# USBC.net
KiCad netlist of a schematic drawn in Altium Designer
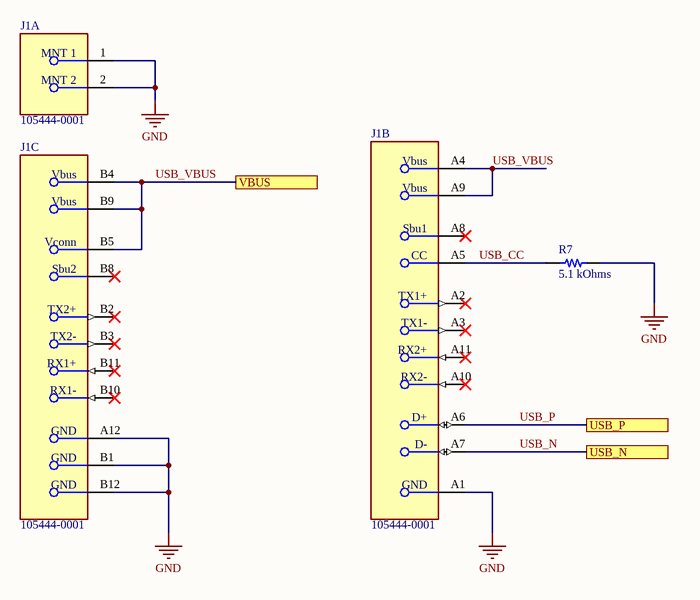
[diagram p0: USBC.SchDoc]

(export (version "E")
  (design (tool "Eeschema 10.0.6"))
  (components
    (comp (ref "J1")
      (value "105444-0001")
      (footprint "FP-105444-0001-MFG")
      (description "CONN PLUG USB3.1 TYPEC BRD EDGE")
      (libsource (lib "Altium Content Vault") (part "182575ff53d3110fee9f5872a599f53"))
    )
    (comp (ref "R7")
      (value "5.1 kOhms")
      (footprint "RES 0603_1608")
      (description "RES 5.1K OHM 0.1% 1/10W 0603")
      (fields (field (name "PART NUMBER") "TNPW06035K10BYEN") (field (name "MANUFACTURER") "Vishay Dale"))
      (libsource (lib "Celestial Altium Library - altium_library") (part "Resistor"))
    )
  )
  (nets
    (net (code "1") (name "/USB_CC") (class "Default")
      (node (ref "J1") (pin "A5") (pinfunction "CC_A5") (pintype "passive"))
      (node (ref "R7") (pin "1") (pinfunction "1_1") (pintype "passive"))
    )
    (net (code "2") (name "/USB_N") (class "Default")
      (node (ref "J1") (pin "A7") (pinfunction "D-_A7") (pintype "bidirectional"))
    )
    (net (code "3") (name "/USB_P") (class "Default")
      (node (ref "J1") (pin "A6") (pinfunction "D+_A6") (pintype "bidirectional"))
    )
    (net (code "4") (name "/USB_VBUS") (class "Default")
      (node (ref "J1") (pin "A4") (pinfunction "Vbus_A4") (pintype "power_in"))
      (node (ref "J1") (pin "A9") (pinfunction "Vbus_A9") (pintype "power_in"))
      (node (ref "J1") (pin "B4") (pinfunction "Vbus_B4") (pintype "power_in"))
      (node (ref "J1") (pin "B5") (pinfunction "Vconn_B5") (pintype "power_in"))
      (node (ref "J1") (pin "B9") (pinfunction "Vbus_B9") (pintype "power_in"))
    )
    (net (code "5") (name "GND") (class "Default")
      (node (ref "J1") (pin "1") (pinfunction "MNT_1_1") (pintype "passive"))
      (node (ref "J1") (pin "2") (pinfunction "MNT_2_2") (pintype "passive"))
      (node (ref "J1") (pin "A1") (pinfunction "GND_A1") (pintype "power_in"))
      (node (ref "J1") (pin "A12") (pinfunction "GND_A12") (pintype "power_in"))
      (node (ref "J1") (pin "B1") (pinfunction "GND_B1") (pintype "power_in"))
      (node (ref "J1") (pin "B12") (pinfunction "GND_B12") (pintype "power_in"))
      (node (ref "R7") (pin "2") (pinfunction "2_2") (pintype "passive"))
    )
    (net (code "6") (name "unconnected-(J1B-RX2+-PadA11)") (class "Default")
      (node (ref "J1") (pin "A11") (pinfunction "RX2+_A11") (pintype "input+no_connect"))
    )
    (net (code "7") (name "unconnected-(J1B-RX2--PadA10)") (class "Default")
      (node (ref "J1") (pin "A10") (pinfunction "RX2-_A10") (pintype "input+no_connect"))
    )
    (net (code "8") (name "unconnected-(J1B-Sbu1-PadA8)") (class "Default")
      (node (ref "J1") (pin "A8") (pinfunction "Sbu1_A8") (pintype "passive+no_connect"))
    )
    (net (code "9") (name "unconnected-(J1B-TX1+-PadA2)") (class "Default")
      (node (ref "J1") (pin "A2") (pinfunction "TX1+_A2") (pintype "output+no_connect"))
    )
    (net (code "10") (name "unconnected-(J1B-TX1--PadA3)") (class "Default")
      (node (ref "J1") (pin "A3") (pinfunction "TX1-_A3") (pintype "output+no_connect"))
    )
    (net (code "11") (name "unconnected-(J1C-RX1+-PadB11)") (class "Default")
      (node (ref "J1") (pin "B11") (pinfunction "RX1+_B11") (pintype "input+no_connect"))
    )
    (net (code "12") (name "unconnected-(J1C-RX1--PadB10)") (class "Default")
      (node (ref "J1") (pin "B10") (pinfunction "RX1-_B10") (pintype "input+no_connect"))
    )
    (net (code "13") (name "unconnected-(J1C-Sbu2-PadB8)") (class "Default")
      (node (ref "J1") (pin "B8") (pinfunction "Sbu2_B8") (pintype "passive+no_connect"))
    )
    (net (code "14") (name "unconnected-(J1C-TX2+-PadB2)") (class "Default")
      (node (ref "J1") (pin "B2") (pinfunction "TX2+_B2") (pintype "output+no_connect"))
    )
    (net (code "15") (name "unconnected-(J1C-TX2--PadB3)") (class "Default")
      (node (ref "J1") (pin "B3") (pinfunction "TX2-_B3") (pintype "output+no_connect"))
    )
  )
)
